# SCH_MAX153_interceptor_2023-03-22.net
KiCad netlist of a schematic drawn in EasyEDA
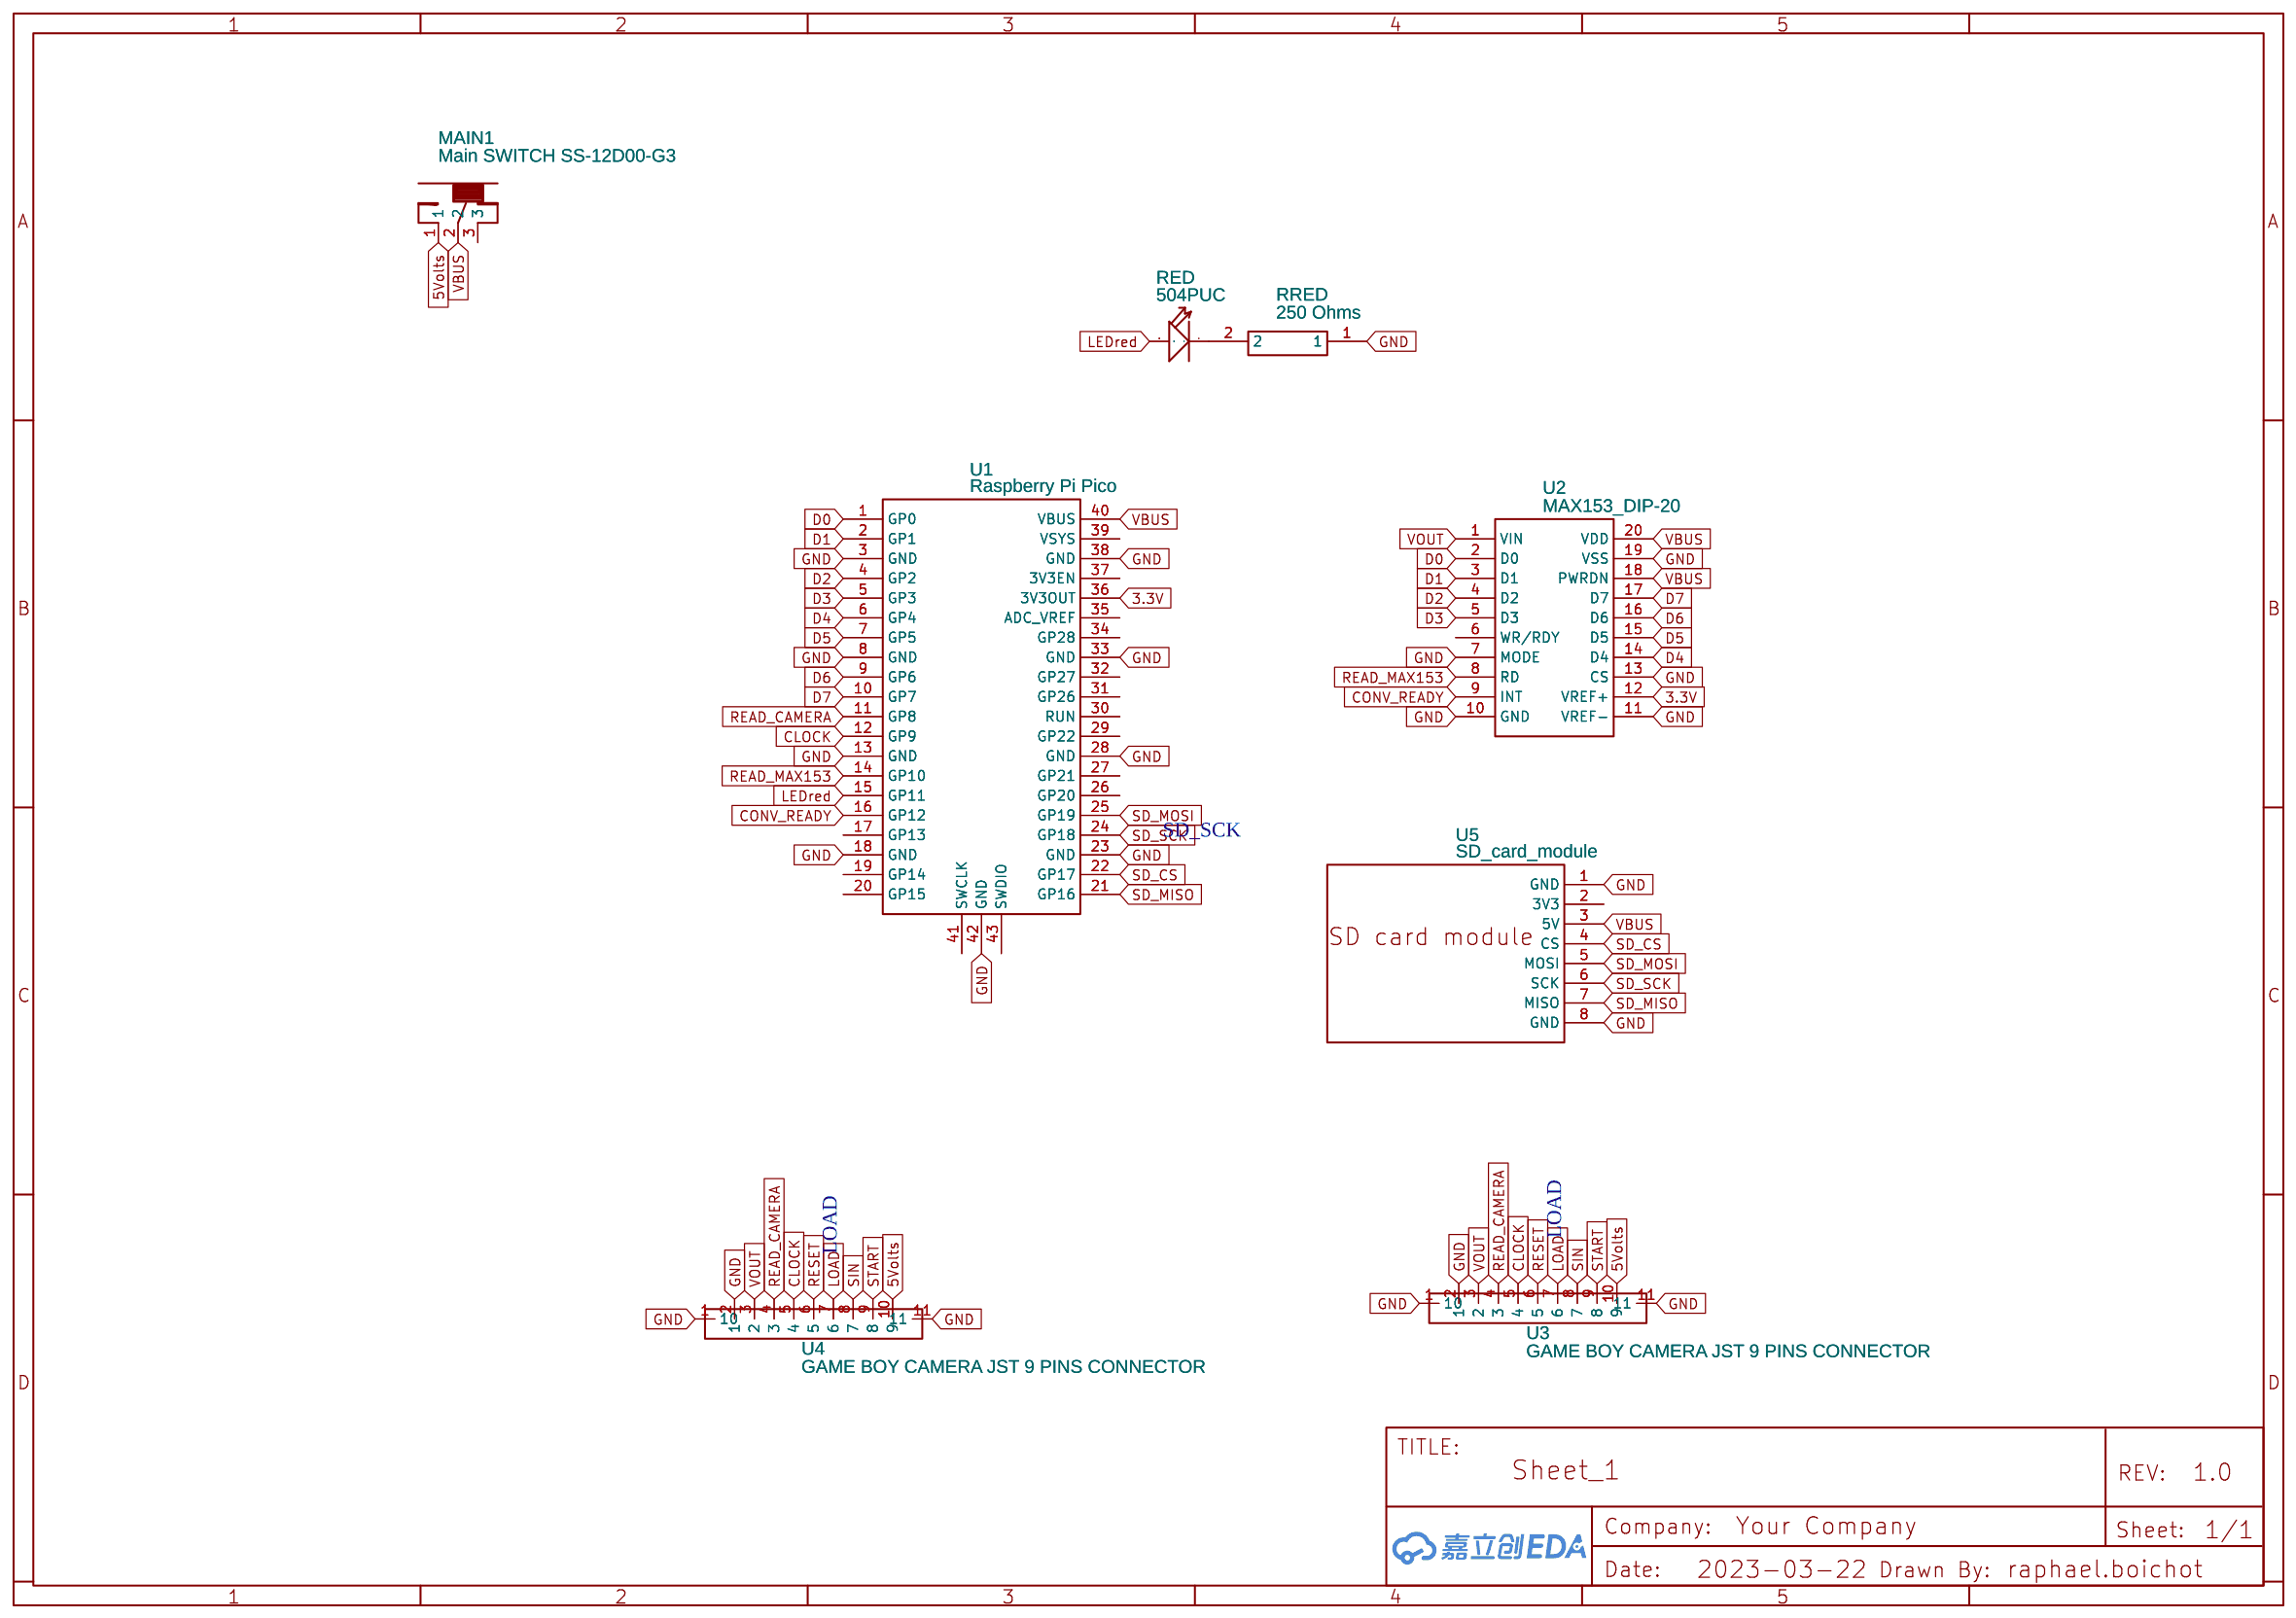
[diagram p0: schematic sheet]

(export (version "E")
  (design (tool "Eeschema 10.0.6"))
  (components
    (comp (ref "MAIN1")
      (value "Main SWITCH SS-12D00-G3")
      (fields (field (name "BOM_Manufacturer Part") "TOGGLE SWITCH SS-12D00-G3"))
      (libsource (lib "") (part "TOGGLE SWITCH SS-12D00-G3"))
    )
    (comp (ref "RED") (value "504PUC") (libsource (lib "") (part "504PUC")))
    (comp (ref "RRED") (value "250 Ohms") (libsource (lib "") (part "RESITOR")))
    (comp (ref "U1") (value "Raspberry Pi Pico") (libsource (lib "") (part "Raspberry Pi Pico")))
    (comp (ref "U2") (value "MAX153_DIP-20") (libsource (lib "") (part "MAX153_DIP-20")))
    (comp (ref "U3")
      (value "GAME BOY CAMERA JST 9 PINS CONNECTOR")
      (libsource (lib "") (part "GAME BOY CAMERA JST 9 PINS CONNECTOR"))
    )
    (comp (ref "U4")
      (value "GAME BOY CAMERA JST 9 PINS CONNECTOR")
      (libsource (lib "") (part "GAME BOY CAMERA JST 9 PINS CONNECTOR"))
    )
    (comp (ref "U5") (value "SD_card_module") (libsource (lib "") (part "SD_card_module")))
  )
  (nets
    (net (code "1") (name "3.3V") (class "Default")
      (node (ref "U1") (pin "36") (pinfunction "3V3OUT_36") (pintype "unspecified"))
      (node (ref "U2") (pin "12") (pinfunction "VREF+_12") (pintype "unspecified"))
    )
    (net (code "2") (name "5Volts") (class "Default")
      (node (ref "MAIN1") (pin "1") (pinfunction "1_1") (pintype "bidirectional"))
      (node (ref "U3") (pin "10") (pinfunction "9_10") (pintype "unspecified"))
      (node (ref "U4") (pin "10") (pinfunction "9_10") (pintype "unspecified"))
    )
    (net (code "3") (name "CLOCK") (class "Default")
      (node (ref "U1") (pin "12") (pinfunction "GP9_12") (pintype "unspecified"))
      (node (ref "U3") (pin "5") (pinfunction "4_5") (pintype "unspecified"))
      (node (ref "U4") (pin "5") (pinfunction "4_5") (pintype "unspecified"))
    )
    (net (code "4") (name "CONV_READY") (class "Default")
      (node (ref "U1") (pin "16") (pinfunction "GP12_16") (pintype "unspecified"))
      (node (ref "U2") (pin "9") (pinfunction "INT_9") (pintype "unspecified"))
    )
    (net (code "5") (name "D0") (class "Default")
      (node (ref "U1") (pin "1") (pinfunction "GP0_1") (pintype "unspecified"))
      (node (ref "U2") (pin "2") (pinfunction "D0_2") (pintype "unspecified"))
    )
    (net (code "6") (name "D1") (class "Default")
      (node (ref "U1") (pin "2") (pinfunction "GP1_2") (pintype "unspecified"))
      (node (ref "U2") (pin "3") (pinfunction "D1_3") (pintype "unspecified"))
    )
    (net (code "7") (name "D2") (class "Default")
      (node (ref "U1") (pin "4") (pinfunction "GP2_4") (pintype "unspecified"))
      (node (ref "U2") (pin "4") (pinfunction "D2_4") (pintype "unspecified"))
    )
    (net (code "8") (name "D3") (class "Default")
      (node (ref "U1") (pin "5") (pinfunction "GP3_5") (pintype "unspecified"))
      (node (ref "U2") (pin "5") (pinfunction "D3_5") (pintype "unspecified"))
    )
    (net (code "9") (name "D4") (class "Default")
      (node (ref "U1") (pin "6") (pinfunction "GP4_6") (pintype "unspecified"))
      (node (ref "U2") (pin "14") (pinfunction "D4_14") (pintype "unspecified"))
    )
    (net (code "10") (name "D5") (class "Default")
      (node (ref "U1") (pin "7") (pinfunction "GP5_7") (pintype "unspecified"))
      (node (ref "U2") (pin "15") (pinfunction "D5_15") (pintype "unspecified"))
    )
    (net (code "11") (name "D6") (class "Default")
      (node (ref "U1") (pin "9") (pinfunction "GP6_9") (pintype "unspecified"))
      (node (ref "U2") (pin "16") (pinfunction "D6_16") (pintype "unspecified"))
    )
    (net (code "12") (name "D7") (class "Default")
      (node (ref "U1") (pin "10") (pinfunction "GP7_10") (pintype "unspecified"))
      (node (ref "U2") (pin "17") (pinfunction "D7_17") (pintype "unspecified"))
    )
    (net (code "13") (name "GND") (class "Default")
      (node (ref "RRED") (pin "1") (pinfunction "1_1") (pintype "unspecified"))
      (node (ref "U1") (pin "13") (pinfunction "GND_13") (pintype "unspecified"))
      (node (ref "U1") (pin "18") (pinfunction "GND_18") (pintype "unspecified"))
      (node (ref "U1") (pin "23") (pinfunction "GND_23") (pintype "unspecified"))
      (node (ref "U1") (pin "28") (pinfunction "GND_28") (pintype "unspecified"))
      (node (ref "U1") (pin "3") (pinfunction "GND_3") (pintype "unspecified"))
      (node (ref "U1") (pin "33") (pinfunction "GND_33") (pintype "unspecified"))
      (node (ref "U1") (pin "38") (pinfunction "GND_38") (pintype "unspecified"))
      (node (ref "U1") (pin "42") (pinfunction "GND_42") (pintype "unspecified"))
      (node (ref "U1") (pin "8") (pinfunction "GND_8") (pintype "unspecified"))
      (node (ref "U2") (pin "10") (pinfunction "GND_10") (pintype "unspecified"))
      (node (ref "U2") (pin "11") (pinfunction "VREF-_11") (pintype "unspecified"))
      (node (ref "U2") (pin "13") (pinfunction "CS_13") (pintype "unspecified"))
      (node (ref "U2") (pin "19") (pinfunction "VSS_19") (pintype "unspecified"))
      (node (ref "U2") (pin "7") (pinfunction "MODE_7") (pintype "unspecified"))
      (node (ref "U3") (pin "1") (pinfunction "10_1") (pintype "unspecified"))
      (node (ref "U3") (pin "11") (pinfunction "11_11") (pintype "unspecified"))
      (node (ref "U3") (pin "2") (pinfunction "1_2") (pintype "unspecified"))
      (node (ref "U4") (pin "1") (pinfunction "10_1") (pintype "unspecified"))
      (node (ref "U4") (pin "11") (pinfunction "11_11") (pintype "unspecified"))
      (node (ref "U4") (pin "2") (pinfunction "1_2") (pintype "unspecified"))
      (node (ref "U5") (pin "1") (pinfunction "GND_1") (pintype "unspecified"))
      (node (ref "U5") (pin "8") (pinfunction "GND_8") (pintype "unspecified"))
    )
    (net (code "14") (name "LEDred") (class "Default")
      (node (ref "RED") (pin "+") (pinfunction "+_+") (pintype "unspecified"))
      (node (ref "U1") (pin "15") (pinfunction "GP11_15") (pintype "unspecified"))
    )
    (net (code "15") (name "LOAD") (class "Default")
      (node (ref "U3") (pin "7") (pinfunction "6_7") (pintype "unspecified"))
      (node (ref "U4") (pin "7") (pinfunction "6_7") (pintype "unspecified"))
    )
    (net (code "16") (name "Net-(RED-Pad-)") (class "Default")
      (node (ref "RED") (pin "-") (pinfunction "-_-") (pintype "unspecified"))
      (node (ref "RRED") (pin "2") (pinfunction "2_2") (pintype "unspecified"))
    )
    (net (code "17") (name "READ_CAMERA") (class "Default")
      (node (ref "U1") (pin "11") (pinfunction "GP8_11") (pintype "unspecified"))
      (node (ref "U3") (pin "4") (pinfunction "3_4") (pintype "unspecified"))
      (node (ref "U4") (pin "4") (pinfunction "3_4") (pintype "unspecified"))
    )
    (net (code "18") (name "READ_MAX153") (class "Default")
      (node (ref "U1") (pin "14") (pinfunction "GP10_14") (pintype "unspecified"))
      (node (ref "U2") (pin "8") (pinfunction "RD_8") (pintype "unspecified"))
    )
    (net (code "19") (name "RESET") (class "Default")
      (node (ref "U3") (pin "6") (pinfunction "5_6") (pintype "unspecified"))
      (node (ref "U4") (pin "6") (pinfunction "5_6") (pintype "unspecified"))
    )
    (net (code "20") (name "SD_CS") (class "Default")
      (node (ref "U1") (pin "22") (pinfunction "GP17_22") (pintype "unspecified"))
      (node (ref "U5") (pin "4") (pinfunction "CS_4") (pintype "unspecified"))
    )
    (net (code "21") (name "SD_MISO") (class "Default")
      (node (ref "U1") (pin "21") (pinfunction "GP16_21") (pintype "unspecified"))
      (node (ref "U5") (pin "7") (pinfunction "MISO_7") (pintype "unspecified"))
    )
    (net (code "22") (name "SD_MOSI") (class "Default")
      (node (ref "U1") (pin "25") (pinfunction "GP19_25") (pintype "unspecified"))
      (node (ref "U5") (pin "5") (pinfunction "MOSI_5") (pintype "unspecified"))
    )
    (net (code "23") (name "SD_SCK") (class "Default")
      (node (ref "U1") (pin "24") (pinfunction "GP18_24") (pintype "unspecified"))
      (node (ref "U5") (pin "6") (pinfunction "SCK_6") (pintype "unspecified"))
    )
    (net (code "24") (name "SIN") (class "Default")
      (node (ref "U3") (pin "8") (pinfunction "7_8") (pintype "unspecified"))
      (node (ref "U4") (pin "8") (pinfunction "7_8") (pintype "unspecified"))
    )
    (net (code "25") (name "START") (class "Default")
      (node (ref "U3") (pin "9") (pinfunction "8_9") (pintype "unspecified"))
      (node (ref "U4") (pin "9") (pinfunction "8_9") (pintype "unspecified"))
    )
    (net (code "26") (name "VBUS") (class "Default")
      (node (ref "MAIN1") (pin "2") (pinfunction "2_2") (pintype "bidirectional"))
      (node (ref "U1") (pin "40") (pinfunction "VBUS_40") (pintype "unspecified"))
      (node (ref "U2") (pin "18") (pinfunction "PWRDN_18") (pintype "unspecified"))
      (node (ref "U2") (pin "20") (pinfunction "VDD_20") (pintype "unspecified"))
      (node (ref "U5") (pin "3") (pinfunction "5V_3") (pintype "unspecified"))
    )
    (net (code "27") (name "VOUT") (class "Default")
      (node (ref "U2") (pin "1") (pinfunction "VIN_1") (pintype "unspecified"))
      (node (ref "U3") (pin "3") (pinfunction "2_3") (pintype "unspecified"))
      (node (ref "U4") (pin "3") (pinfunction "2_3") (pintype "unspecified"))
    )
    (net (code "28") (name "unconnected-(MAIN1-Pad3)") (class "Default")
      (node (ref "MAIN1") (pin "3") (pinfunction "3_3") (pintype "unspecified"))
    )
    (net (code "29") (name "unconnected-(U1-3V3EN-Pad37)") (class "Default")
      (node (ref "U1") (pin "37") (pinfunction "3V3EN_37") (pintype "unspecified"))
    )
    (net (code "30") (name "unconnected-(U1-ADC_VREF-Pad35)") (class "Default")
      (node (ref "U1") (pin "35") (pinfunction "ADC_VREF_35") (pintype "unspecified"))
    )
    (net (code "31") (name "unconnected-(U1-GP13-Pad17)") (class "Default")
      (node (ref "U1") (pin "17") (pinfunction "GP13_17") (pintype "unspecified"))
    )
    (net (code "32") (name "unconnected-(U1-GP14-Pad19)") (class "Default")
      (node (ref "U1") (pin "19") (pinfunction "GP14_19") (pintype "unspecified"))
    )
    (net (code "33") (name "unconnected-(U1-GP15-Pad20)") (class "Default")
      (node (ref "U1") (pin "20") (pinfunction "GP15_20") (pintype "unspecified"))
    )
    (net (code "34") (name "unconnected-(U1-GP20-Pad26)") (class "Default")
      (node (ref "U1") (pin "26") (pinfunction "GP20_26") (pintype "unspecified"))
    )
    (net (code "35") (name "unconnected-(U1-GP21-Pad27)") (class "Default")
      (node (ref "U1") (pin "27") (pinfunction "GP21_27") (pintype "unspecified"))
    )
    (net (code "36") (name "unconnected-(U1-GP22-Pad29)") (class "Default")
      (node (ref "U1") (pin "29") (pinfunction "GP22_29") (pintype "unspecified"))
    )
    (net (code "37") (name "unconnected-(U1-GP26-Pad31)") (class "Default")
      (node (ref "U1") (pin "31") (pinfunction "GP26_31") (pintype "unspecified"))
    )
    (net (code "38") (name "unconnected-(U1-GP27-Pad32)") (class "Default")
      (node (ref "U1") (pin "32") (pinfunction "GP27_32") (pintype "unspecified"))
    )
    (net (code "39") (name "unconnected-(U1-GP28-Pad34)") (class "Default")
      (node (ref "U1") (pin "34") (pinfunction "GP28_34") (pintype "unspecified"))
    )
    (net (code "40") (name "unconnected-(U1-RUN-Pad30)") (class "Default")
      (node (ref "U1") (pin "30") (pinfunction "RUN_30") (pintype "unspecified"))
    )
    (net (code "41") (name "unconnected-(U1-SWCLK-Pad41)") (class "Default")
      (node (ref "U1") (pin "41") (pinfunction "SWCLK_41") (pintype "unspecified"))
    )
    (net (code "42") (name "unconnected-(U1-SWDIO-Pad43)") (class "Default")
      (node (ref "U1") (pin "43") (pinfunction "SWDIO_43") (pintype "unspecified"))
    )
    (net (code "43") (name "unconnected-(U1-VSYS-Pad39)") (class "Default")
      (node (ref "U1") (pin "39") (pinfunction "VSYS_39") (pintype "unspecified"))
    )
    (net (code "44") (name "unconnected-(U2-WR{slash}RDY-Pad6)") (class "Default")
      (node (ref "U2") (pin "6") (pinfunction "WR/RDY_6") (pintype "unspecified"))
    )
    (net (code "45") (name "unconnected-(U5-3V3-Pad2)") (class "Default")
      (node (ref "U5") (pin "2") (pinfunction "3V3_2") (pintype "unspecified"))
    )
  )
)
